# Sheet1.net
KiCad netlist of a schematic drawn in Altium Designer
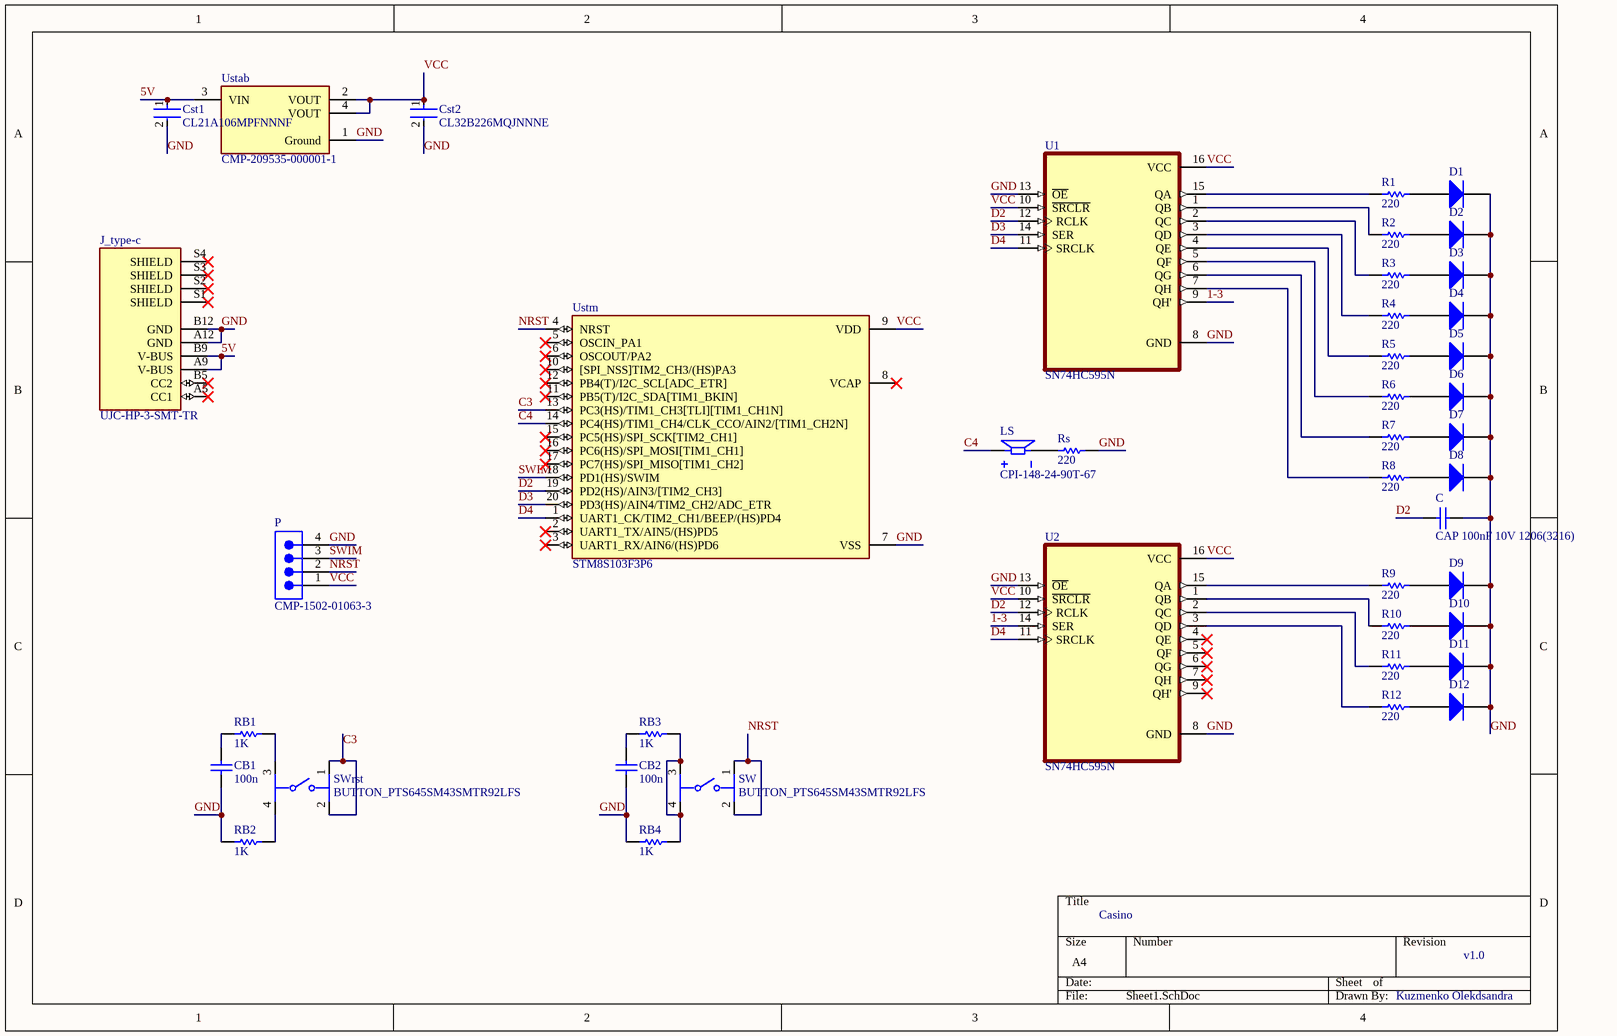
[diagram p0: Sheet1.SchDoc]

(export (version "E")
  (design (tool "Eeschema 10.0.6"))
  (components
    (comp (ref "C")
      (value "CAP 100nF 10V 1206(3216)")
      (footprint "CAPC1206(3216)100_M")
      (description "CAP 100nF 10V ±5% 1206 (3216 Metric) Thickness 1mm SMD")
      (fields (field (name "TOLERANCE") "Â±5%"))
      (libsource (lib "Altium Content Vault") (part "CAP"))
    )
    (comp (ref "CB1")
      (value "100n")
      (description "Capacitor")
      (libsource (lib "Simulation Generic Components") (part "Capacitor"))
    )
    (comp (ref "CB2")
      (value "100n")
      (description "Capacitor")
      (libsource (lib "Simulation Generic Components") (part "Capacitor"))
    )
    (comp (ref "Cst1")
      (value "CL21A106MPFNNNF")
      (footprint "FP-CL21-IPC_C")
      (description "CL21 Series 0805 10uF 10V ±20% Tolerance X5R Multilayer Ceramic Chip Capacitor")
      (fields (field (name "TOLERANCE") "20%"))
      (libsource (lib "Altium Content Vault") (part "b4654b650e69147ec39a6b967a45e02"))
    )
    (comp (ref "Cst2")
      (value "CL32B226MQJNNNE")
      (footprint "FP-CL32-IPC_B")
      (description "Cap Ceramic 22uF 6.3V X7R ±20% SMD 1210 +125°C Embossed T/R")
      (fields (field (name "TOLERANCE") "20%"))
      (libsource (lib "Altium Content Vault") (part "b4654b650e69147ec39a6b967a45e02"))
    )
    (comp (ref "D1") (value "Diode") (libsource (lib "Simulation Generic Components") (part "Diode")))
    (comp (ref "D2") (value "Diode") (libsource (lib "Simulation Generic Components") (part "Diode")))
    (comp (ref "D3") (value "Diode") (libsource (lib "Simulation Generic Components") (part "Diode")))
    (comp (ref "D4") (value "Diode") (libsource (lib "Simulation Generic Components") (part "Diode")))
    (comp (ref "D5") (value "Diode") (libsource (lib "Simulation Generic Components") (part "Diode")))
    (comp (ref "D6") (value "Diode") (libsource (lib "Simulation Generic Components") (part "Diode")))
    (comp (ref "D7") (value "Diode") (libsource (lib "Simulation Generic Components") (part "Diode")))
    (comp (ref "D8") (value "Diode") (libsource (lib "Simulation Generic Components") (part "Diode")))
    (comp (ref "D9") (value "Diode") (libsource (lib "Simulation Generic Components") (part "Diode")))
    (comp (ref "D10") (value "Diode") (libsource (lib "Simulation Generic Components") (part "Diode")))
    (comp (ref "D11") (value "Diode") (libsource (lib "Simulation Generic Components") (part "Diode")))
    (comp (ref "D12") (value "Diode") (libsource (lib "Simulation Generic Components") (part "Diode")))
    (comp (ref "J_type-c")
      (value "UJC-HP-3-SMT-TR")
      (footprint "CUI_UJC-HP-3-SMT-TR")
      (libsource (lib "National Technical University of Ukraine Igor Sikorsky Kyiv Polytechnic Institute- Educator Program") (part "UJC-HP-3-SMT-TR"))
    )
    (comp (ref "LS")
      (value "CPI-148-24-90T-67")
      (footprint "XDCR_CPI-148-24-90T-67")
      (fields (field (name "MF") "Same Sky"))
      (libsource (lib "National Technical University of Ukraine Igor Sikorsky Kyiv Polytechnic Institute- Educator Program") (part "CPI-148-24-90T-67"))
    )
    (comp (ref "P")
      (value "CMP-1502-01063-3")
      (footprint "61300411021")
      (libsource (lib "National Technical University of Ukraine Igor Sikorsky Kyiv Polytechnic Institute- Educator Program") (part "CMP-1502-01063-3"))
    )
    (comp (ref "R1")
      (value "220")
      (description "Resistor")
      (libsource (lib "Simulation Generic Components") (part "Resistor"))
    )
    (comp (ref "R2")
      (value "220")
      (description "Resistor")
      (libsource (lib "Simulation Generic Components") (part "Resistor"))
    )
    (comp (ref "R3")
      (value "220")
      (description "Resistor")
      (libsource (lib "Simulation Generic Components") (part "Resistor"))
    )
    (comp (ref "R4")
      (value "220")
      (description "Resistor")
      (libsource (lib "Simulation Generic Components") (part "Resistor"))
    )
    (comp (ref "R5")
      (value "220")
      (description "Resistor")
      (libsource (lib "Simulation Generic Components") (part "Resistor"))
    )
    (comp (ref "R6")
      (value "220")
      (description "Resistor")
      (libsource (lib "Simulation Generic Components") (part "Resistor"))
    )
    (comp (ref "R7")
      (value "220")
      (description "Resistor")
      (libsource (lib "Simulation Generic Components") (part "Resistor"))
    )
    (comp (ref "R8")
      (value "220")
      (description "Resistor")
      (libsource (lib "Simulation Generic Components") (part "Resistor"))
    )
    (comp (ref "R9")
      (value "220")
      (description "Resistor")
      (libsource (lib "Simulation Generic Components") (part "Resistor"))
    )
    (comp (ref "R10")
      (value "220")
      (description "Resistor")
      (libsource (lib "Simulation Generic Components") (part "Resistor"))
    )
    (comp (ref "R11")
      (value "220")
      (description "Resistor")
      (libsource (lib "Simulation Generic Components") (part "Resistor"))
    )
    (comp (ref "R12")
      (value "220")
      (description "Resistor")
      (libsource (lib "Simulation Generic Components") (part "Resistor"))
    )
    (comp (ref "RB1")
      (value "1K")
      (description "Resistor")
      (libsource (lib "Simulation Generic Components") (part "Resistor"))
    )
    (comp (ref "RB2")
      (value "1K")
      (description "Resistor")
      (libsource (lib "Simulation Generic Components") (part "Resistor"))
    )
    (comp (ref "RB3")
      (value "1K")
      (description "Resistor")
      (libsource (lib "Simulation Generic Components") (part "Resistor"))
    )
    (comp (ref "RB4")
      (value "1K")
      (description "Resistor")
      (libsource (lib "Simulation Generic Components") (part "Resistor"))
    )
    (comp (ref "Rs")
      (value "220")
      (description "Resistor")
      (libsource (lib "Simulation Generic Components") (part "Resistor"))
    )
    (comp (ref "SW")
      (value "BUTTON_PTS645SM43SMTR92LFS")
      (footprint "FP-PTS645SM43SMTR92LFS-MFG")
      (libsource (lib "National Technical University of Ukraine Igor Sikorsky Kyiv Polytechnic Institute- Educator Program") (part "1adf0dd01260c80cf25a44bfd6b99ba"))
    )
    (comp (ref "SWrst")
      (value "BUTTON_PTS645SM43SMTR92LFS")
      (footprint "FP-PTS645SM43SMTR92LFS-MFG")
      (libsource (lib "National Technical University of Ukraine Igor Sikorsky Kyiv Polytechnic Institute- Educator Program") (part "1adf0dd01260c80cf25a44bfd6b99ba"))
    )
    (comp (ref "U1")
      (value "SN74HC595N")
      (footprint "DIP794W45P254L1969H508Q16")
      (description "8-bit shift registers with 3-state output registers")
      (fields (field (name "MF") "Texas Instruments"))
      (libsource (lib "National Technical University of Ukraine Igor Sikorsky Kyiv Polytechnic Institute- Educator Program") (part "SN74HC595N"))
    )
    (comp (ref "U2")
      (value "SN74HC595N")
      (footprint "DIP794W45P254L1969H508Q16")
      (description "8-bit shift registers with 3-state output registers")
      (fields (field (name "MF") "Texas Instruments"))
      (libsource (lib "National Technical University of Ukraine Igor Sikorsky Kyiv Polytechnic Institute- Educator Program") (part "SN74HC595N"))
    )
    (comp (ref "Ustab")
      (value "CMP-209535-000001-1")
      (footprint "FP-AMS1117-IPC_A")
      (description "LDO Voltage Regulators 1A, 3.3V")
      (fields
        (field (name "MANUFACTURER") "Advanced Monolithic Systems")
        (field (name "OCTOPART") "https://octopart.com/ams1117-3.3-advanced+monolithic+systems-25899300")
      )
      (libsource (lib "National Technical University of Ukraine Igor Sikorsky Kyiv Polytechnic Institute- Educator Program") (part "CMP-209535-000001-1"))
    )
    (comp (ref "Ustm")
      (value "STM8S103F3P6")
      (footprint "SOP65P640X120-20N")
      (description "STM8 series Microcontroller IC 8-Bit 16MHz 8KB (8K x 8) FLASH 20-TSSOP")
      (fields (field (name "MF") "STMicroelectronics"))
      (libsource (lib "National Technical University of Ukraine Igor Sikorsky Kyiv Polytechnic Institute- Educator Program") (part "STM8S103F3P6"))
    )
  )
  (nets
    (net (code "1") (name "/1-3") (class "Default")
      (node (ref "U1") (pin "9") (pinfunction "QH'_9") (pintype "output"))
      (node (ref "U2") (pin "14") (pinfunction "SER_14") (pintype "input"))
    )
    (net (code "2") (name "/5V") (class "Default")
      (node (ref "Cst1") (pin "1") (pinfunction "1_1") (pintype "passive"))
      (node (ref "J_type-c") (pin "A9") (pinfunction "V-BUS_A9") (pintype "power_in"))
      (node (ref "J_type-c") (pin "B9") (pinfunction "V-BUS_B9") (pintype "power_in"))
      (node (ref "Ustab") (pin "3") (pinfunction "VIN_3") (pintype "power_in"))
    )
    (net (code "3") (name "/C3") (class "Default")
      (node (ref "SWrst") (pin "1") (pinfunction "1_1") (pintype "passive"))
      (node (ref "SWrst") (pin "2") (pinfunction "2_2") (pintype "passive"))
      (node (ref "Ustm") (pin "13") (pinfunction "PC3(HS)/TIM1_CH3[TLI][TIM1_CH1N]_13") (pintype "bidirectional"))
    )
    (net (code "4") (name "/C4") (class "Default")
      (node (ref "LS") (pin "P") (pinfunction "P_P") (pintype "passive"))
      (node (ref "Ustm") (pin "14") (pinfunction "PC4(HS)/TIM1_CH4/CLK_CCO/AIN2/[TIM1_CH2N]_14") (pintype "bidirectional"))
    )
    (net (code "5") (name "/D2") (class "Default")
      (node (ref "C") (pin "1") (pinfunction "1_1") (pintype "passive"))
      (node (ref "U1") (pin "12") (pinfunction "RCLK_12") (pintype "input"))
      (node (ref "U2") (pin "12") (pinfunction "RCLK_12") (pintype "input"))
      (node (ref "Ustm") (pin "19") (pinfunction "PD2(HS)/AIN3/[TIM2_CH3]_19") (pintype "bidirectional"))
    )
    (net (code "6") (name "/D3") (class "Default")
      (node (ref "U1") (pin "14") (pinfunction "SER_14") (pintype "input"))
      (node (ref "Ustm") (pin "20") (pinfunction "PD3(HS)/AIN4/TIM2_CH2/ADC_ETR_20") (pintype "bidirectional"))
    )
    (net (code "7") (name "/D4") (class "Default")
      (node (ref "U1") (pin "11") (pinfunction "SRCLK_11") (pintype "input"))
      (node (ref "U2") (pin "11") (pinfunction "SRCLK_11") (pintype "input"))
      (node (ref "Ustm") (pin "1") (pinfunction "UART1_CK/TIM2_CH1/BEEP/(HS)PD4_1") (pintype "bidirectional"))
    )
    (net (code "8") (name "/GND") (class "Default")
      (node (ref "C") (pin "2") (pinfunction "2_2") (pintype "passive"))
      (node (ref "CB1") (pin "1") (pinfunction "1_1") (pintype "passive"))
      (node (ref "CB2") (pin "1") (pinfunction "1_1") (pintype "passive"))
      (node (ref "Cst1") (pin "2") (pinfunction "2_2") (pintype "passive"))
      (node (ref "Cst2") (pin "2") (pinfunction "2_2") (pintype "passive"))
      (node (ref "D1") (pin "2") (pinfunction "K_2") (pintype "passive"))
      (node (ref "D10") (pin "2") (pinfunction "K_2") (pintype "passive"))
      (node (ref "D11") (pin "2") (pinfunction "K_2") (pintype "passive"))
      (node (ref "D12") (pin "2") (pinfunction "K_2") (pintype "passive"))
      (node (ref "D2") (pin "2") (pinfunction "K_2") (pintype "passive"))
      (node (ref "D3") (pin "2") (pinfunction "K_2") (pintype "passive"))
      (node (ref "D4") (pin "2") (pinfunction "K_2") (pintype "passive"))
      (node (ref "D5") (pin "2") (pinfunction "K_2") (pintype "passive"))
      (node (ref "D6") (pin "2") (pinfunction "K_2") (pintype "passive"))
      (node (ref "D7") (pin "2") (pinfunction "K_2") (pintype "passive"))
      (node (ref "D8") (pin "2") (pinfunction "K_2") (pintype "passive"))
      (node (ref "D9") (pin "2") (pinfunction "K_2") (pintype "passive"))
      (node (ref "J_type-c") (pin "A12") (pinfunction "GND_A12") (pintype "power_in"))
      (node (ref "J_type-c") (pin "B12") (pinfunction "GND_B12") (pintype "power_in"))
      (node (ref "P") (pin "4") (pinfunction "4_4") (pintype "passive"))
      (node (ref "RB2") (pin "2") (pinfunction "2_2") (pintype "passive"))
      (node (ref "RB4") (pin "1") (pinfunction "1_1") (pintype "passive"))
      (node (ref "Rs") (pin "1") (pinfunction "1_1") (pintype "passive"))
      (node (ref "U1") (pin "13") (pinfunction "~{OE}_13") (pintype "input"))
      (node (ref "U1") (pin "8") (pinfunction "GND_8") (pintype "power_in"))
      (node (ref "U2") (pin "13") (pinfunction "~{OE}_13") (pintype "input"))
      (node (ref "U2") (pin "8") (pinfunction "GND_8") (pintype "power_in"))
      (node (ref "Ustab") (pin "1") (pinfunction "Ground_1") (pintype "power_in"))
      (node (ref "Ustm") (pin "7") (pinfunction "VSS_7") (pintype "power_in"))
    )
    (net (code "9") (name "/NRST") (class "Default")
      (node (ref "P") (pin "2") (pinfunction "2_2") (pintype "passive"))
      (node (ref "SW") (pin "1") (pinfunction "1_1") (pintype "passive"))
      (node (ref "SW") (pin "2") (pinfunction "2_2") (pintype "passive"))
      (node (ref "Ustm") (pin "4") (pinfunction "NRST_4") (pintype "bidirectional"))
    )
    (net (code "10") (name "/SWIM") (class "Default")
      (node (ref "P") (pin "3") (pinfunction "3_3") (pintype "passive"))
      (node (ref "Ustm") (pin "18") (pinfunction "PD1(HS)/SWIM_18") (pintype "bidirectional"))
    )
    (net (code "11") (name "/VCC") (class "Default")
      (node (ref "Cst2") (pin "1") (pinfunction "1_1") (pintype "passive"))
      (node (ref "P") (pin "1") (pinfunction "1_1") (pintype "passive"))
      (node (ref "U1") (pin "10") (pinfunction "~{SRCLR}_10") (pintype "input"))
      (node (ref "U1") (pin "16") (pinfunction "VCC_16") (pintype "power_in"))
      (node (ref "U2") (pin "10") (pinfunction "~{SRCLR}_10") (pintype "input"))
      (node (ref "U2") (pin "16") (pinfunction "VCC_16") (pintype "power_in"))
      (node (ref "Ustab") (pin "2") (pinfunction "VOUT_2") (pintype "passive"))
      (node (ref "Ustab") (pin "4") (pinfunction "VOUT_4") (pintype "passive"))
      (node (ref "Ustm") (pin "9") (pinfunction "VDD_9") (pintype "power_in"))
    )
    (net (code "12") (name "Net-(CB1-Pad2)") (class "Default")
      (node (ref "CB1") (pin "2") (pinfunction "2_2") (pintype "passive"))
      (node (ref "RB1") (pin "2") (pinfunction "2_2") (pintype "passive"))
    )
    (net (code "13") (name "Net-(CB2-Pad2)") (class "Default")
      (node (ref "CB2") (pin "2") (pinfunction "2_2") (pintype "passive"))
      (node (ref "RB3") (pin "2") (pinfunction "2_2") (pintype "passive"))
    )
    (net (code "14") (name "Net-(D1-A)") (class "Default")
      (node (ref "D1") (pin "1") (pinfunction "A_1") (pintype "passive"))
      (node (ref "R1") (pin "2") (pinfunction "2_2") (pintype "passive"))
    )
    (net (code "15") (name "Net-(D2-A)") (class "Default")
      (node (ref "D2") (pin "1") (pinfunction "A_1") (pintype "passive"))
      (node (ref "R2") (pin "2") (pinfunction "2_2") (pintype "passive"))
    )
    (net (code "16") (name "Net-(D3-A)") (class "Default")
      (node (ref "D3") (pin "1") (pinfunction "A_1") (pintype "passive"))
      (node (ref "R3") (pin "2") (pinfunction "2_2") (pintype "passive"))
    )
    (net (code "17") (name "Net-(D4-A)") (class "Default")
      (node (ref "D4") (pin "1") (pinfunction "A_1") (pintype "passive"))
      (node (ref "R4") (pin "2") (pinfunction "2_2") (pintype "passive"))
    )
    (net (code "18") (name "Net-(D5-A)") (class "Default")
      (node (ref "D5") (pin "1") (pinfunction "A_1") (pintype "passive"))
      (node (ref "R5") (pin "2") (pinfunction "2_2") (pintype "passive"))
    )
    (net (code "19") (name "Net-(D6-A)") (class "Default")
      (node (ref "D6") (pin "1") (pinfunction "A_1") (pintype "passive"))
      (node (ref "R6") (pin "2") (pinfunction "2_2") (pintype "passive"))
    )
    (net (code "20") (name "Net-(D7-A)") (class "Default")
      (node (ref "D7") (pin "1") (pinfunction "A_1") (pintype "passive"))
      (node (ref "R7") (pin "2") (pinfunction "2_2") (pintype "passive"))
    )
    (net (code "21") (name "Net-(D8-A)") (class "Default")
      (node (ref "D8") (pin "1") (pinfunction "A_1") (pintype "passive"))
      (node (ref "R8") (pin "2") (pinfunction "2_2") (pintype "passive"))
    )
    (net (code "22") (name "Net-(D9-A)") (class "Default")
      (node (ref "D9") (pin "1") (pinfunction "A_1") (pintype "passive"))
      (node (ref "R9") (pin "2") (pinfunction "2_2") (pintype "passive"))
    )
    (net (code "23") (name "Net-(D10-A)") (class "Default")
      (node (ref "D10") (pin "1") (pinfunction "A_1") (pintype "passive"))
      (node (ref "R10") (pin "2") (pinfunction "2_2") (pintype "passive"))
    )
    (net (code "24") (name "Net-(D11-A)") (class "Default")
      (node (ref "D11") (pin "1") (pinfunction "A_1") (pintype "passive"))
      (node (ref "R11") (pin "2") (pinfunction "2_2") (pintype "passive"))
    )
    (net (code "25") (name "Net-(D12-A)") (class "Default")
      (node (ref "D12") (pin "1") (pinfunction "A_1") (pintype "passive"))
      (node (ref "R12") (pin "2") (pinfunction "2_2") (pintype "passive"))
    )
    (net (code "26") (name "Net-(LS-PadN)") (class "Default")
      (node (ref "LS") (pin "N") (pinfunction "N_N") (pintype "passive"))
      (node (ref "Rs") (pin "2") (pinfunction "2_2") (pintype "passive"))
    )
    (net (code "27") (name "Net-(RB1-Pad1)") (class "Default")
      (node (ref "RB1") (pin "1") (pinfunction "1_1") (pintype "passive"))
      (node (ref "SWrst") (pin "3") (pinfunction "3_3") (pintype "passive"))
    )
    (net (code "28") (name "Net-(RB2-Pad1)") (class "Default")
      (node (ref "RB2") (pin "1") (pinfunction "1_1") (pintype "passive"))
      (node (ref "SWrst") (pin "4") (pinfunction "4_4") (pintype "passive"))
    )
    (net (code "29") (name "Net-(RB3-Pad1)") (class "Default")
      (node (ref "RB3") (pin "1") (pinfunction "1_1") (pintype "passive"))
      (node (ref "RB4") (pin "2") (pinfunction "2_2") (pintype "passive"))
      (node (ref "SW") (pin "3") (pinfunction "3_3") (pintype "passive"))
      (node (ref "SW") (pin "4") (pinfunction "4_4") (pintype "passive"))
    )
    (net (code "30") (name "Net-(U1-QA)") (class "Default")
      (node (ref "R1") (pin "1") (pinfunction "1_1") (pintype "passive"))
      (node (ref "U1") (pin "15") (pinfunction "QA_15") (pintype "output"))
    )
    (net (code "31") (name "Net-(U1-QB)") (class "Default")
      (node (ref "R2") (pin "1") (pinfunction "1_1") (pintype "passive"))
      (node (ref "U1") (pin "1") (pinfunction "QB_1") (pintype "output"))
    )
    (net (code "32") (name "Net-(U1-QC)") (class "Default")
      (node (ref "R3") (pin "1") (pinfunction "1_1") (pintype "passive"))
      (node (ref "U1") (pin "2") (pinfunction "QC_2") (pintype "output"))
    )
    (net (code "33") (name "Net-(U1-QD)") (class "Default")
      (node (ref "R4") (pin "1") (pinfunction "1_1") (pintype "passive"))
      (node (ref "U1") (pin "3") (pinfunction "QD_3") (pintype "output"))
    )
    (net (code "34") (name "Net-(U1-QE)") (class "Default")
      (node (ref "R5") (pin "1") (pinfunction "1_1") (pintype "passive"))
      (node (ref "U1") (pin "4") (pinfunction "QE_4") (pintype "output"))
    )
    (net (code "35") (name "Net-(U1-QF)") (class "Default")
      (node (ref "R6") (pin "1") (pinfunction "1_1") (pintype "passive"))
      (node (ref "U1") (pin "5") (pinfunction "QF_5") (pintype "output"))
    )
    (net (code "36") (name "Net-(U1-QG)") (class "Default")
      (node (ref "R7") (pin "1") (pinfunction "1_1") (pintype "passive"))
      (node (ref "U1") (pin "6") (pinfunction "QG_6") (pintype "output"))
    )
    (net (code "37") (name "Net-(U1-QH)") (class "Default")
      (node (ref "R8") (pin "1") (pinfunction "1_1") (pintype "passive"))
      (node (ref "U1") (pin "7") (pinfunction "QH_7") (pintype "output"))
    )
    (net (code "38") (name "Net-(U2-QA)") (class "Default")
      (node (ref "R9") (pin "1") (pinfunction "1_1") (pintype "passive"))
      (node (ref "U2") (pin "15") (pinfunction "QA_15") (pintype "output"))
    )
    (net (code "39") (name "Net-(U2-QB)") (class "Default")
      (node (ref "R10") (pin "1") (pinfunction "1_1") (pintype "passive"))
      (node (ref "U2") (pin "1") (pinfunction "QB_1") (pintype "output"))
    )
    (net (code "40") (name "Net-(U2-QC)") (class "Default")
      (node (ref "R11") (pin "1") (pinfunction "1_1") (pintype "passive"))
      (node (ref "U2") (pin "2") (pinfunction "QC_2") (pintype "output"))
    )
    (net (code "41") (name "Net-(U2-QD)") (class "Default")
      (node (ref "R12") (pin "1") (pinfunction "1_1") (pintype "passive"))
      (node (ref "U2") (pin "3") (pinfunction "QD_3") (pintype "output"))
    )
    (net (code "42") (name "unconnected-(J_type-c-CC1-PadA5)") (class "Default")
      (node (ref "J_type-c") (pin "A5") (pinfunction "CC1_A5") (pintype "bidirectional+no_connect"))
    )
    (net (code "43") (name "unconnected-(J_type-c-CC2-PadB5)") (class "Default")
      (node (ref "J_type-c") (pin "B5") (pinfunction "CC2_B5") (pintype "bidirectional+no_connect"))
    )
    (net (code "44") (name "unconnected-(J_type-c-SHIELD-PadS1)") (class "Default")
      (node (ref "J_type-c") (pin "S1") (pinfunction "SHIELD_S1") (pintype "passive+no_connect"))
    )
    (net (code "45") (name "unconnected-(J_type-c-SHIELD-PadS2)") (class "Default")
      (node (ref "J_type-c") (pin "S2") (pinfunction "SHIELD_S2") (pintype "passive+no_connect"))
    )
    (net (code "46") (name "unconnected-(J_type-c-SHIELD-PadS3)") (class "Default")
      (node (ref "J_type-c") (pin "S3") (pinfunction "SHIELD_S3") (pintype "passive+no_connect"))
    )
    (net (code "47") (name "unconnected-(J_type-c-SHIELD-PadS4)") (class "Default")
      (node (ref "J_type-c") (pin "S4") (pinfunction "SHIELD_S4") (pintype "passive+no_connect"))
    )
    (net (code "48") (name "unconnected-(U2-QE-Pad4)") (class "Default")
      (node (ref "U2") (pin "4") (pinfunction "QE_4") (pintype "output+no_connect"))
    )
    (net (code "49") (name "unconnected-(U2-QF-Pad5)") (class "Default")
      (node (ref "U2") (pin "5") (pinfunction "QF_5") (pintype "output+no_connect"))
    )
    (net (code "50") (name "unconnected-(U2-QG-Pad6)") (class "Default")
      (node (ref "U2") (pin "6") (pinfunction "QG_6") (pintype "output+no_connect"))
    )
    (net (code "51") (name "unconnected-(U2-QH'-Pad9)") (class "Default")
      (node (ref "U2") (pin "9") (pinfunction "QH'_9") (pintype "output+no_connect"))
    )
    (net (code "52") (name "unconnected-(U2-QH-Pad7)") (class "Default")
      (node (ref "U2") (pin "7") (pinfunction "QH_7") (pintype "output+no_connect"))
    )
    (net (code "53") (name "unconnected-(Ustm-OSCIN_PA1-Pad5)") (class "Default")
      (node (ref "Ustm") (pin "5") (pinfunction "OSCIN_PA1_5") (pintype "bidirectional+no_connect"))
    )
    (net (code "54") (name "unconnected-(Ustm-OSCOUT{slash}PA2-Pad6)") (class "Default")
      (node (ref "Ustm") (pin "6") (pinfunction "OSCOUT/PA2_6") (pintype "bidirectional+no_connect"))
    )
    (net (code "55") (name "unconnected-(Ustm-PB4(T){slash}I2C_SCL[ADC_ETR]-Pad12)") (class "Default")
      (node (ref "Ustm") (pin "12") (pinfunction "PB4(T)/I2C_SCL[ADC_ETR]_12") (pintype "bidirectional+no_connect"))
    )
    (net (code "56") (name "unconnected-(Ustm-PB5(T){slash}I2C_SDA[TIM1_BKIN]-Pad11)") (class "Default")
      (node (ref "Ustm") (pin "11") (pinfunction "PB5(T)/I2C_SDA[TIM1_BKIN]_11") (pintype "bidirectional+no_connect"))
    )
    (net (code "57") (name "unconnected-(Ustm-PC5(HS){slash}SPI_SCK[TIM2_CH1]-Pad15)") (class "Default")
      (node (ref "Ustm") (pin "15") (pinfunction "PC5(HS)/SPI_SCK[TIM2_CH1]_15") (pintype "bidirectional+no_connect"))
    )
    (net (code "58") (name "unconnected-(Ustm-PC6(HS){slash}SPI_MOSI[TIM1_CH1]-Pad16)") (class "Default")
      (node (ref "Ustm") (pin "16") (pinfunction "PC6(HS)/SPI_MOSI[TIM1_CH1]_16") (pintype "bidirectional+no_connect"))
    )
    (net (code "59") (name "unconnected-(Ustm-PC7(HS){slash}SPI_MISO[TIM1_CH2]-Pad17)") (class "Default")
      (node (ref "Ustm") (pin "17") (pinfunction "PC7(HS)/SPI_MISO[TIM1_CH2]_17") (pintype "bidirectional+no_connect"))
    )
    (net (code "60") (name "unconnected-(Ustm-UART1_RX{slash}AIN6{slash}(HS)PD6-Pad3)") (class "Default")
      (node (ref "Ustm") (pin "3") (pinfunction "UART1_RX/AIN6/(HS)PD6_3") (pintype "bidirectional+no_connect"))
    )
    (net (code "61") (name "unconnected-(Ustm-UART1_TX{slash}AIN5{slash}(HS)PD5-Pad2)") (class "Default")
      (node (ref "Ustm") (pin "2") (pinfunction "UART1_TX/AIN5/(HS)PD5_2") (pintype "bidirectional+no_connect"))
    )
    (net (code "62") (name "unconnected-(Ustm-VCAP-Pad8)") (class "Default")
      (node (ref "Ustm") (pin "8") (pinfunction "VCAP_8") (pintype "passive+no_connect"))
    )
    (net (code "63") (name "unconnected-(Ustm-[SPI_NSS]TIM2_CH3{slash}(HS)PA3-Pad10)") (class "Default")
      (node (ref "Ustm") (pin "10") (pinfunction "[SPI_NSS]TIM2_CH3/(HS)PA3_10") (pintype "bidirectional+no_connect"))
    )
  )
)
